# LM704A0_3V3_PINOUT.net
KiCad netlist of a schematic drawn in Altium Designer
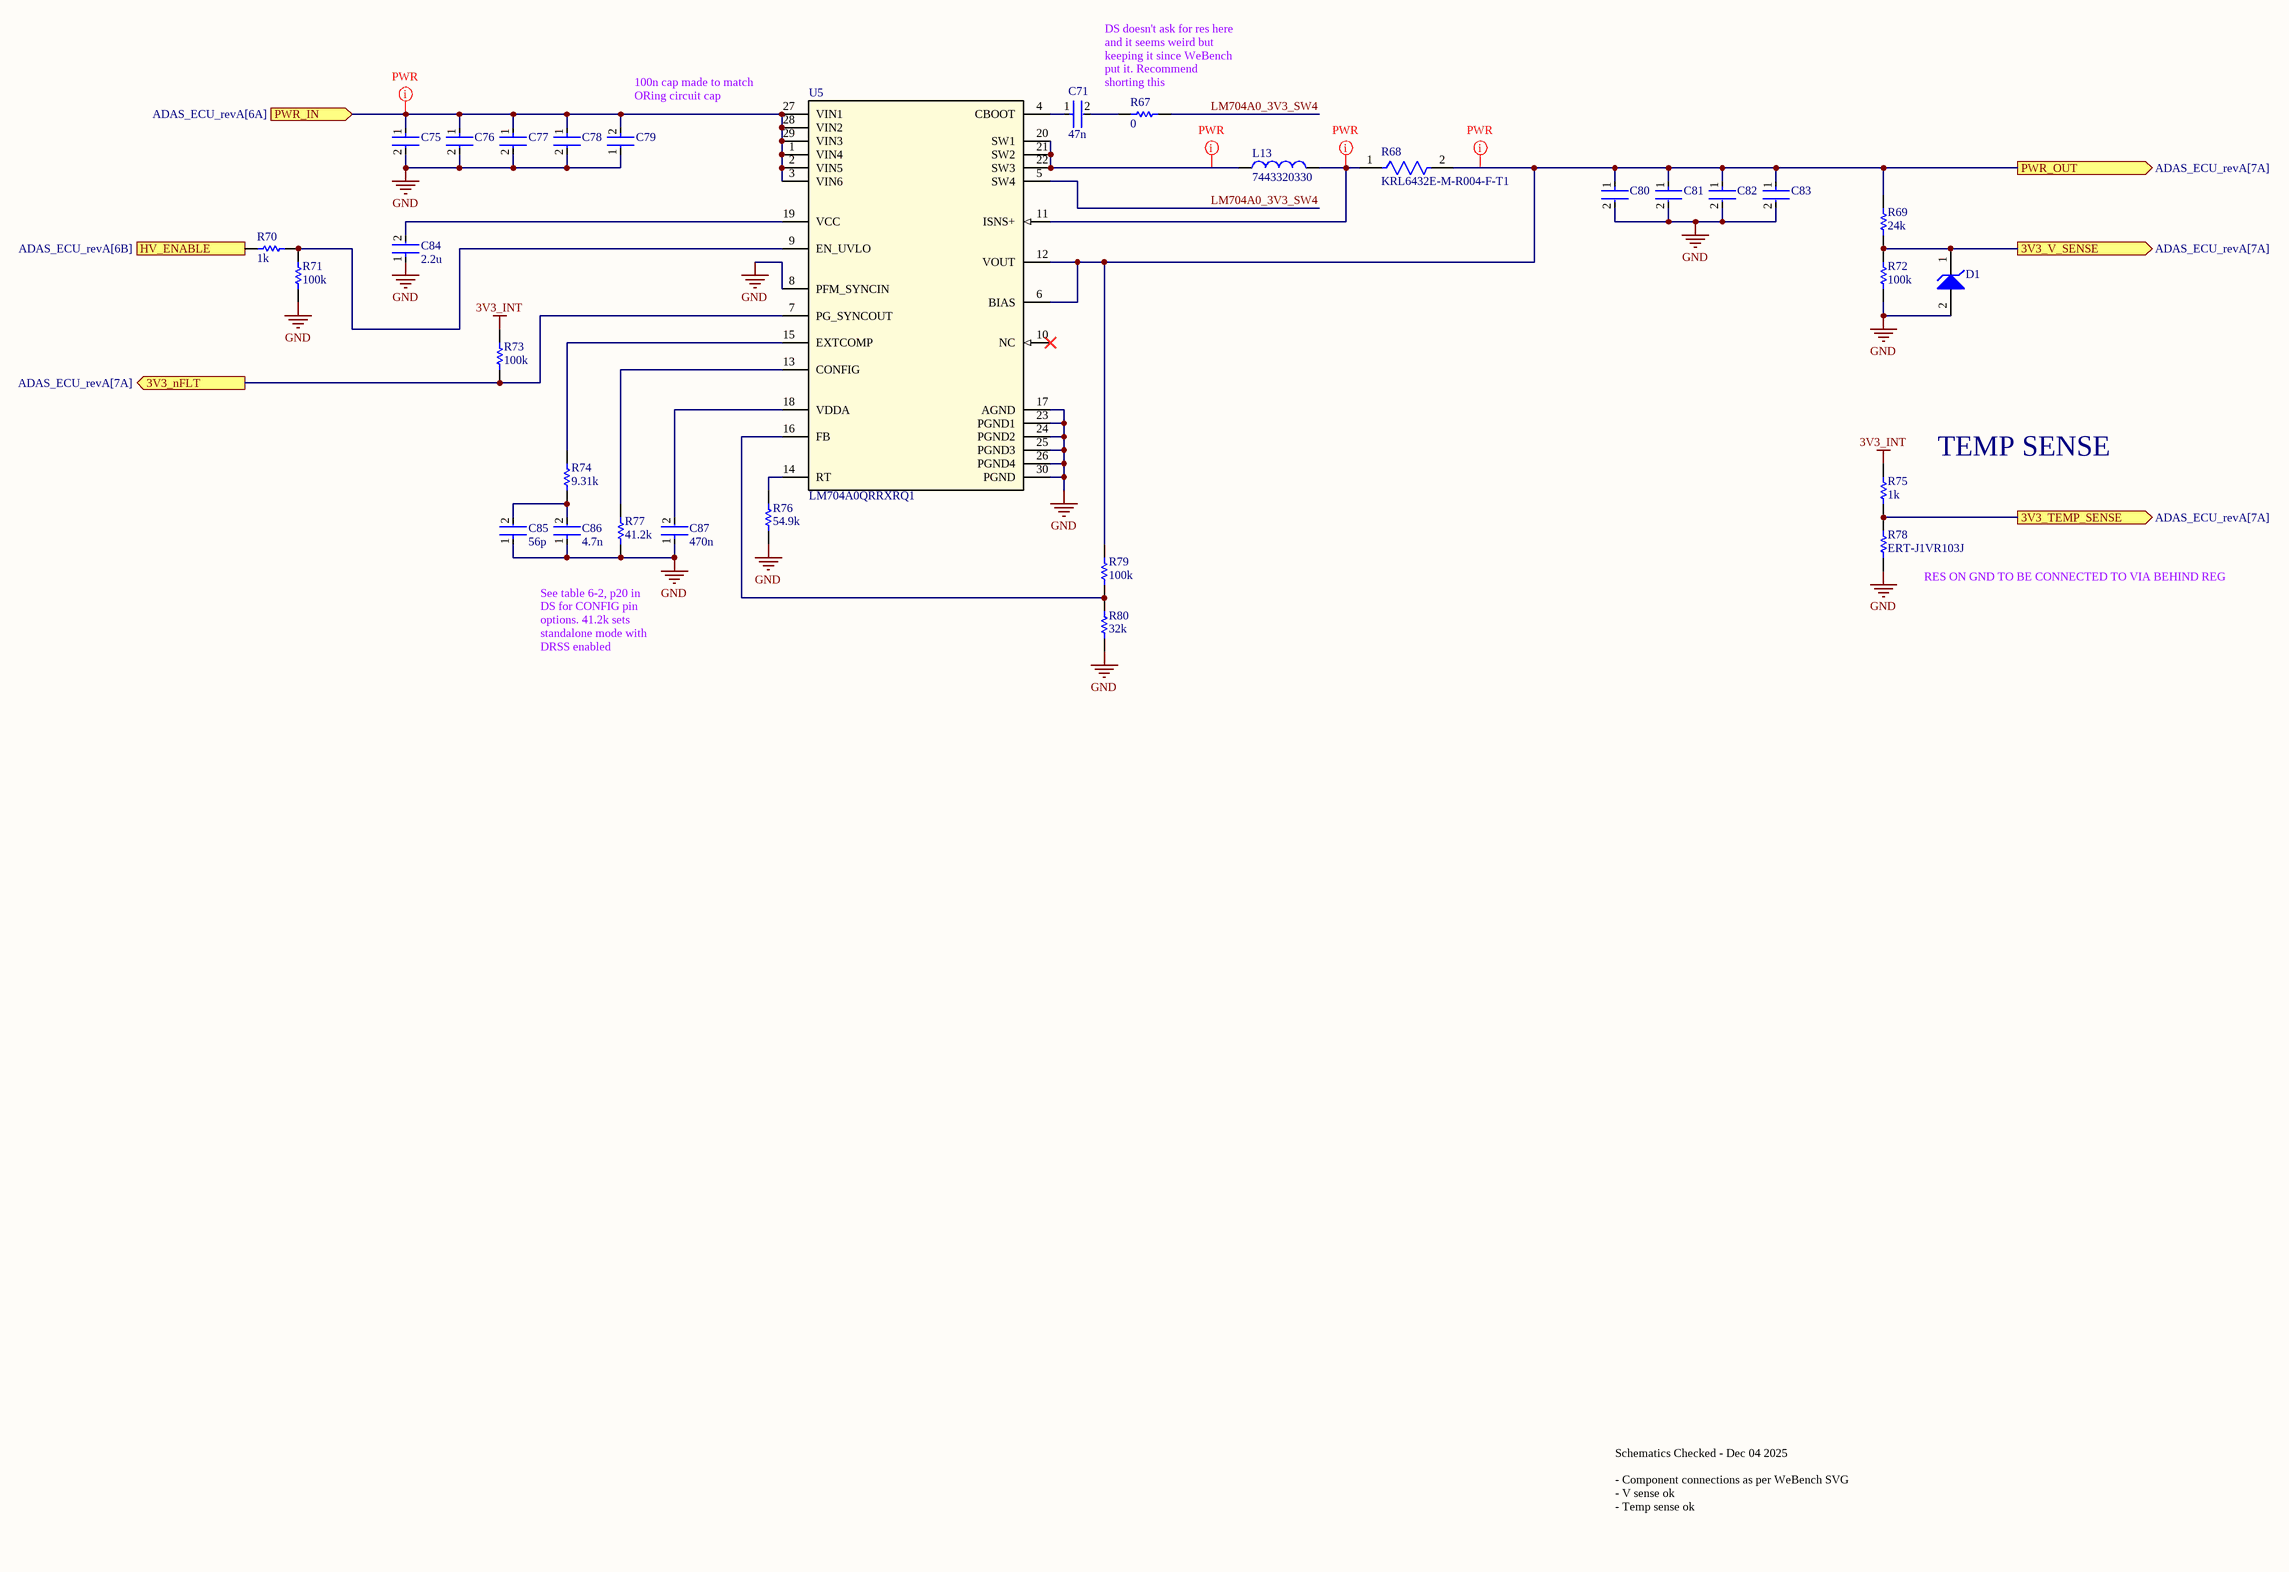
[diagram p0: LM704A0_3V3_PINOUT.SchDoc]

(export (version "E")
  (design (tool "Eeschema 10.0.6"))
  (components
    (comp (ref "C71")
      (value "47n")
      (footprint "FP-0402-L_1_0_0_05-W_0_5-IPC_A")
      (description "LARGE PADS, 0402 CAP, CHANGE COMMENT TO MATCH REAL P/N")
      (libsource (lib "Space Concordia") (part "b4654b650e69147ec39a6b967a45e02"))
    )
    (comp (ref "C75")
      (value "C3225X7R1H106M250AC")
      (footprint "FP-C3225-250-0_4-MFG")
      (description "Multilayer Ceramic Capacitors 10uF ±20% 50V X7R SMD 1210")
      (fields (field (name "TOLERANCE") "20%"))
      (libsource (lib "Altium Content Vault") (part "02cd4be3c70576c341d710602a673aa"))
    )
    (comp (ref "C76")
      (value "C3225X7R1H106M250AC")
      (footprint "FP-C3225-250-0_4-MFG")
      (description "Multilayer Ceramic Capacitors 10uF ±20% 50V X7R SMD 1210")
      (fields (field (name "TOLERANCE") "20%"))
      (libsource (lib "Altium Content Vault") (part "02cd4be3c70576c341d710602a673aa"))
    )
    (comp (ref "C77")
      (value "C3225X7R1H106M250AC")
      (footprint "FP-C3225-250-0_4-MFG")
      (description "Multilayer Ceramic Capacitors 10uF ±20% 50V X7R SMD 1210")
      (fields (field (name "TOLERANCE") "20%"))
      (libsource (lib "Altium Content Vault") (part "02cd4be3c70576c341d710602a673aa"))
    )
    (comp (ref "C78")
      (value "C3225X7R1H106M250AC")
      (footprint "FP-C3225-250-0_4-MFG")
      (description "Multilayer Ceramic Capacitors 10uF ±20% 50V X7R SMD 1210")
      (fields (field (name "TOLERANCE") "20%"))
      (libsource (lib "Altium Content Vault") (part "02cd4be3c70576c341d710602a673aa"))
    )
    (comp (ref "C79")
      (value "AC1210KKX7R0BB104")
      (footprint "FP-AC1210-0_85-MFG")
      (description "CAP CER 0.1UF 100V X7R 1210")
      (fields (field (name "MANUFACTURER") "Yageo") (field (name "TOLERANCE") "0.1"))
      (libsource (lib "Altium Content Vault") (part "236180d848d6139a670b325ea6854c9"))
    )
    (comp (ref "C80")
      (value "GRM32EC80J107ME20L")
      (footprint "FP-GRM32E-0_3-0_2-IPC_C")
      (description "DIFF P/N 100UF 6.3V GRM32EC80J107ME20L")
      (fields (field (name "VOLTAGE") "16V") (field (name "TOLERANCE") "10%"))
      (libsource (lib "Altium Content Vault") (part "b4654b650e69147ec39a6b967a45e02"))
    )
    (comp (ref "C81")
      (value "GRM32EC80J107ME20L")
      (footprint "FP-GRM32E-0_3-0_2-IPC_C")
      (description "DIFF P/N 100UF 6.3V GRM32EC80J107ME20L")
      (fields (field (name "VOLTAGE") "16V") (field (name "TOLERANCE") "10%"))
      (libsource (lib "Altium Content Vault") (part "b4654b650e69147ec39a6b967a45e02"))
    )
    (comp (ref "C82")
      (value "GRM32EC80J107ME20L")
      (footprint "FP-GRM32E-0_3-0_2-IPC_C")
      (description "DIFF P/N 100UF 6.3V GRM32EC80J107ME20L")
      (fields (field (name "VOLTAGE") "16V") (field (name "TOLERANCE") "10%"))
      (libsource (lib "Altium Content Vault") (part "b4654b650e69147ec39a6b967a45e02"))
    )
    (comp (ref "C83")
      (value "GRM32EC80J107ME20L")
      (footprint "FP-GRM32E-0_3-0_2-IPC_C")
      (description "DIFF P/N 100UF 6.3V GRM32EC80J107ME20L")
      (fields (field (name "VOLTAGE") "16V") (field (name "TOLERANCE") "10%"))
      (libsource (lib "Altium Content Vault") (part "b4654b650e69147ec39a6b967a45e02"))
    )
    (comp (ref "C84")
      (value "2.2u")
      (footprint "FP-0402-L_1_0_0_05-W_0_5-IPC_A")
      (description "LARGE PADS, 0402 CAP, CHANGE COMMENT TO MATCH REAL P/N")
      (libsource (lib "Space Concordia") (part "b4654b650e69147ec39a6b967a45e02"))
    )
    (comp (ref "C85")
      (value "56p")
      (footprint "FP-0402-L_1_0_0_05-W_0_5-IPC_A")
      (description "LARGE PADS, 0402 CAP, CHANGE COMMENT TO MATCH REAL P/N")
      (libsource (lib "Space Concordia") (part "b4654b650e69147ec39a6b967a45e02"))
    )
    (comp (ref "C86")
      (value "4.7n")
      (footprint "FP-0402-L_1_0_0_05-W_0_5-IPC_A")
      (description "LARGE PADS, 0402 CAP, CHANGE COMMENT TO MATCH REAL P/N")
      (libsource (lib "Space Concordia") (part "b4654b650e69147ec39a6b967a45e02"))
    )
    (comp (ref "C87")
      (value "470n")
      (footprint "FP-0402-L_1_0_0_05-W_0_5-IPC_A")
      (description "LARGE PADS, 0402 CAP, CHANGE COMMENT TO MATCH REAL P/N")
      (libsource (lib "Space Concordia") (part "b4654b650e69147ec39a6b967a45e02"))
    )
    (comp (ref "D1")
      (value "DNP/MM5Z3V3T1G")
      (footprint "ONSC-SOD-523-2-502-01_V")
      (description "Zener Voltage Regulator, 500 mW, 2-Pin SOD-523, Pb-Free, Tape and Reel")
      (fields (field (name "MANUFACTURER") "On Semiconductor") (field (name "PARTNUMBER") "MM5Z3V3T1G"))
      (libsource (lib "Altium Content Vault") (part "ONSC-K1A2-2"))
    )
    (comp (ref "L13")
      (value "7443320330")
      (footprint "WE-HCC_1210")
      (libsource (lib "Altium Content Vault") (part "Inductor - 1"))
    )
    (comp (ref "R67")
      (value "0")
      (footprint "R0603B")
      (description "Resistor")
      (libsource (lib "Space Concordia") (part "Resistor"))
    )
    (comp (ref "R68")
      (value "KRL6432E-M-R004-F-T1")
      (footprint "FP-KRL6432E-MFG")
      (description "KRL6432E-M-R004-F-T1 Metal Foil Low Resistance Chip Resistor (long-side terminal), 2512, RoHS")
      (fields (field (name "TOLERANCE") "1%"))
      (libsource (lib "Altium Content Vault") (part "1029c3af85768c4190bb7ad29bc67b5"))
    )
    (comp (ref "R69")
      (value "24k")
      (footprint "R0603B")
      (description "Resistor")
      (libsource (lib "Space Concordia") (part "Resistor"))
    )
    (comp (ref "R70")
      (value "1k")
      (footprint "R0603B")
      (description "Resistor")
      (libsource (lib "Space Concordia") (part "Resistor"))
    )
    (comp (ref "R71")
      (value "100k")
      (footprint "R0603B")
      (description "Resistor")
      (libsource (lib "Space Concordia") (part "Resistor"))
    )
    (comp (ref "R72")
      (value "100k")
      (footprint "R0603B")
      (description "Resistor")
      (libsource (lib "Space Concordia") (part "Resistor"))
    )
    (comp (ref "R73")
      (value "100k")
      (footprint "R0603B")
      (description "Resistor")
      (libsource (lib "Space Concordia") (part "Resistor"))
    )
    (comp (ref "R74")
      (value "9.31k")
      (footprint "R0603B")
      (description "Resistor")
      (libsource (lib "Space Concordia") (part "Resistor"))
    )
    (comp (ref "R75")
      (value "1k")
      (footprint "R0603B")
      (description "Resistor")
      (libsource (lib "Space Concordia") (part "Resistor"))
    )
    (comp (ref "R76")
      (value "54.9k")
      (footprint "R0603B")
      (description "Resistor")
      (libsource (lib "Space Concordia") (part "Resistor"))
    )
    (comp (ref "R77")
      (value "41.2k")
      (footprint "R0603B")
      (description "Resistor")
      (libsource (lib "Space Concordia") (part "Resistor"))
    )
    (comp (ref "R78")
      (value "ERT-J1VR103J")
      (footprint "RESC1608X90X30ML15T20")
      (fields (field (name "MANUFACTURER") "Panasonic"))
      (libsource (lib "Altium Content Vault") (part "RES"))
    )
    (comp (ref "R79")
      (value "100k")
      (footprint "R0603B")
      (description "Resistor")
      (libsource (lib "Space Concordia") (part "Resistor"))
    )
    (comp (ref "R80")
      (value "32k")
      (footprint "R0603B")
      (description "Resistor")
      (libsource (lib "Space Concordia") (part "Resistor"))
    )
    (comp (ref "U5")
      (value "LM704A0QRRXRQ1")
      (footprint "LM704A0QRRXRQ1-Footprint-1")
      (libsource (lib "Space Concordia") (part "LM704A0QRRXRQ1"))
    )
  )
  (nets
    (net (code "1") (name "/3V3_TEMP_SENSE") (class "Default")
      (node (ref "R75") (pin "2") (pinfunction "2_2") (pintype "passive"))
      (node (ref "R78") (pin "2") (pinfunction "2_2") (pintype "passive"))
    )
    (net (code "2") (name "/3V3_V_SENSE") (class "Default")
      (node (ref "D1") (pin "1") (pinfunction "K_1") (pintype "passive"))
      (node (ref "R69") (pin "2") (pinfunction "2_2") (pintype "passive"))
      (node (ref "R72") (pin "1") (pinfunction "1_1") (pintype "passive"))
    )
    (net (code "3") (name "/3V3_nFLT") (class "Default")
      (node (ref "R73") (pin "1") (pinfunction "1_1") (pintype "passive"))
      (node (ref "U5") (pin "7") (pinfunction "PG_SYNCOUT_7") (pintype "passive"))
    )
    (net (code "4") (name "/HV_ENABLE") (class "Default")
      (node (ref "R70") (pin "2") (pinfunction "2_2") (pintype "passive"))
    )
    (net (code "5") (name "/LM704A0_3V3_SW4") (class "Default")
      (node (ref "R67") (pin "2") (pinfunction "2_2") (pintype "passive"))
      (node (ref "U5") (pin "5") (pinfunction "SW4_5") (pintype "power_in"))
    )
    (net (code "6") (name "/PWR_IN") (class "Default")
      (node (ref "C75") (pin "1") (pinfunction "1_1") (pintype "passive"))
      (node (ref "C76") (pin "1") (pinfunction "1_1") (pintype "passive"))
      (node (ref "C77") (pin "1") (pinfunction "1_1") (pintype "passive"))
      (node (ref "C78") (pin "1") (pinfunction "1_1") (pintype "passive"))
      (node (ref "C79") (pin "2") (pinfunction "2_2") (pintype "passive"))
      (node (ref "U5") (pin "1") (pinfunction "VIN4_1") (pintype "passive"))
      (node (ref "U5") (pin "2") (pinfunction "VIN5_2") (pintype "passive"))
      (node (ref "U5") (pin "27") (pinfunction "VIN1_27") (pintype "power_in"))
      (node (ref "U5") (pin "28") (pinfunction "VIN2_28") (pintype "power_in"))
      (node (ref "U5") (pin "29") (pinfunction "VIN3_29") (pintype "power_in"))
      (node (ref "U5") (pin "3") (pinfunction "VIN6_3") (pintype "power_in"))
    )
    (net (code "7") (name "/PWR_OUT") (class "Default")
      (node (ref "C80") (pin "1") (pinfunction "1_1") (pintype "passive"))
      (node (ref "C81") (pin "1") (pinfunction "1_1") (pintype "passive"))
      (node (ref "C82") (pin "1") (pinfunction "1_1") (pintype "passive"))
      (node (ref "C83") (pin "1") (pinfunction "1_1") (pintype "passive"))
      (node (ref "R68") (pin "2") (pinfunction "2_2") (pintype "passive"))
      (node (ref "R69") (pin "1") (pinfunction "1_1") (pintype "passive"))
      (node (ref "R79") (pin "1") (pinfunction "1_1") (pintype "passive"))
      (node (ref "U5") (pin "12") (pinfunction "VOUT_12") (pintype "passive"))
      (node (ref "U5") (pin "6") (pinfunction "BIAS_6") (pintype "passive"))
    )
    (net (code "8") (name "3V3_INT") (class "Default")
      (node (ref "R73") (pin "2") (pinfunction "2_2") (pintype "passive"))
      (node (ref "R75") (pin "1") (pinfunction "1_1") (pintype "passive"))
    )
    (net (code "9") (name "GND") (class "Default")
      (node (ref "C75") (pin "2") (pinfunction "2_2") (pintype "passive"))
      (node (ref "C76") (pin "2") (pinfunction "2_2") (pintype "passive"))
      (node (ref "C77") (pin "2") (pinfunction "2_2") (pintype "passive"))
      (node (ref "C78") (pin "2") (pinfunction "2_2") (pintype "passive"))
      (node (ref "C79") (pin "1") (pinfunction "1_1") (pintype "passive"))
      (node (ref "C80") (pin "2") (pinfunction "2_2") (pintype "passive"))
      (node (ref "C81") (pin "2") (pinfunction "2_2") (pintype "passive"))
      (node (ref "C82") (pin "2") (pinfunction "2_2") (pintype "passive"))
      (node (ref "C83") (pin "2") (pinfunction "2_2") (pintype "passive"))
      (node (ref "C84") (pin "1") (pinfunction "1_1") (pintype "passive"))
      (node (ref "C85") (pin "1") (pinfunction "1_1") (pintype "passive"))
      (node (ref "C86") (pin "1") (pinfunction "1_1") (pintype "passive"))
      (node (ref "C87") (pin "1") (pinfunction "1_1") (pintype "passive"))
      (node (ref "D1") (pin "2") (pinfunction "A_2") (pintype "passive"))
      (node (ref "R71") (pin "1") (pinfunction "1_1") (pintype "passive"))
      (node (ref "R72") (pin "2") (pinfunction "2_2") (pintype "passive"))
      (node (ref "R76") (pin "2") (pinfunction "2_2") (pintype "passive"))
      (node (ref "R77") (pin "2") (pinfunction "2_2") (pintype "passive"))
      (node (ref "R78") (pin "1") (pinfunction "1_1") (pintype "passive"))
      (node (ref "R80") (pin "2") (pinfunction "2_2") (pintype "passive"))
      (node (ref "U5") (pin "17") (pinfunction "AGND_17") (pintype "passive"))
      (node (ref "U5") (pin "23") (pinfunction "PGND1_23") (pintype "passive"))
      (node (ref "U5") (pin "24") (pinfunction "PGND2_24") (pintype "passive"))
      (node (ref "U5") (pin "25") (pinfunction "PGND3_25") (pintype "power_in"))
      (node (ref "U5") (pin "26") (pinfunction "PGND4_26") (pintype "power_in"))
      (node (ref "U5") (pin "30") (pinfunction "PGND_30") (pintype "power_in"))
      (node (ref "U5") (pin "8") (pinfunction "PFM_SYNCIN_8") (pintype "power_in"))
    )
    (net (code "10") (name "Net-(C71-Pad2)") (class "Default")
      (node (ref "C71") (pin "2") (pinfunction "2_2") (pintype "passive"))
      (node (ref "R67") (pin "1") (pinfunction "1_1") (pintype "passive"))
    )
    (net (code "11") (name "Net-(C85-Pad2)") (class "Default")
      (node (ref "C85") (pin "2") (pinfunction "2_2") (pintype "passive"))
      (node (ref "C86") (pin "2") (pinfunction "2_2") (pintype "passive"))
      (node (ref "R74") (pin "2") (pinfunction "2_2") (pintype "passive"))
    )
    (net (code "12") (name "Net-(U5-CBOOT)") (class "Default")
      (node (ref "C71") (pin "1") (pinfunction "1_1") (pintype "passive"))
      (node (ref "U5") (pin "4") (pinfunction "CBOOT_4") (pintype "power_in"))
    )
    (net (code "13") (name "Net-(U5-CONFIG)") (class "Default")
      (node (ref "R77") (pin "1") (pinfunction "1_1") (pintype "passive"))
      (node (ref "U5") (pin "13") (pinfunction "CONFIG_13") (pintype "passive"))
    )
    (net (code "14") (name "Net-(U5-EN_UVLO)") (class "Default")
      (node (ref "R70") (pin "1") (pinfunction "1_1") (pintype "passive"))
      (node (ref "R71") (pin "2") (pinfunction "2_2") (pintype "passive"))
      (node (ref "U5") (pin "9") (pinfunction "EN_UVLO_9") (pintype "open_collector"))
    )
    (net (code "15") (name "Net-(U5-EXTCOMP)") (class "Default")
      (node (ref "R74") (pin "1") (pinfunction "1_1") (pintype "passive"))
      (node (ref "U5") (pin "15") (pinfunction "EXTCOMP_15") (pintype "passive"))
    )
    (net (code "16") (name "Net-(U5-FB)") (class "Default")
      (node (ref "R79") (pin "2") (pinfunction "2_2") (pintype "passive"))
      (node (ref "R80") (pin "1") (pinfunction "1_1") (pintype "passive"))
      (node (ref "U5") (pin "16") (pinfunction "FB_16") (pintype "passive"))
    )
    (net (code "17") (name "Net-(U5-ISNS+)") (class "Default")
      (node (ref "L13") (pin "2") (pinfunction "2_2") (pintype "passive"))
      (node (ref "R68") (pin "1") (pinfunction "1_1") (pintype "passive"))
      (node (ref "U5") (pin "11") (pinfunction "ISNS+_11") (pintype "input"))
    )
    (net (code "18") (name "Net-(U5-RT)") (class "Default")
      (node (ref "R76") (pin "1") (pinfunction "1_1") (pintype "passive"))
      (node (ref "U5") (pin "14") (pinfunction "RT_14") (pintype "passive"))
    )
    (net (code "19") (name "Net-(U5-SW1)") (class "Default")
      (node (ref "L13") (pin "1") (pinfunction "1_1") (pintype "passive"))
      (node (ref "U5") (pin "20") (pinfunction "SW1_20") (pintype "power_in"))
      (node (ref "U5") (pin "21") (pinfunction "SW2_21") (pintype "power_in"))
      (node (ref "U5") (pin "22") (pinfunction "SW3_22") (pintype "passive"))
    )
    (net (code "20") (name "Net-(U5-VCC)") (class "Default")
      (node (ref "C84") (pin "2") (pinfunction "2_2") (pintype "passive"))
      (node (ref "U5") (pin "19") (pinfunction "VCC_19") (pintype "power_in"))
    )
    (net (code "21") (name "Net-(U5-VDDA)") (class "Default")
      (node (ref "C87") (pin "2") (pinfunction "2_2") (pintype "passive"))
      (node (ref "U5") (pin "18") (pinfunction "VDDA_18") (pintype "passive"))
    )
    (net (code "22") (name "unconnected-(U5-NC-Pad10)") (class "Default")
      (node (ref "U5") (pin "10") (pinfunction "NC_10") (pintype "input+no_connect"))
    )
  )
)
